# LEDS_BUTTONS.net
KiCad netlist of a schematic drawn in Altium Designer
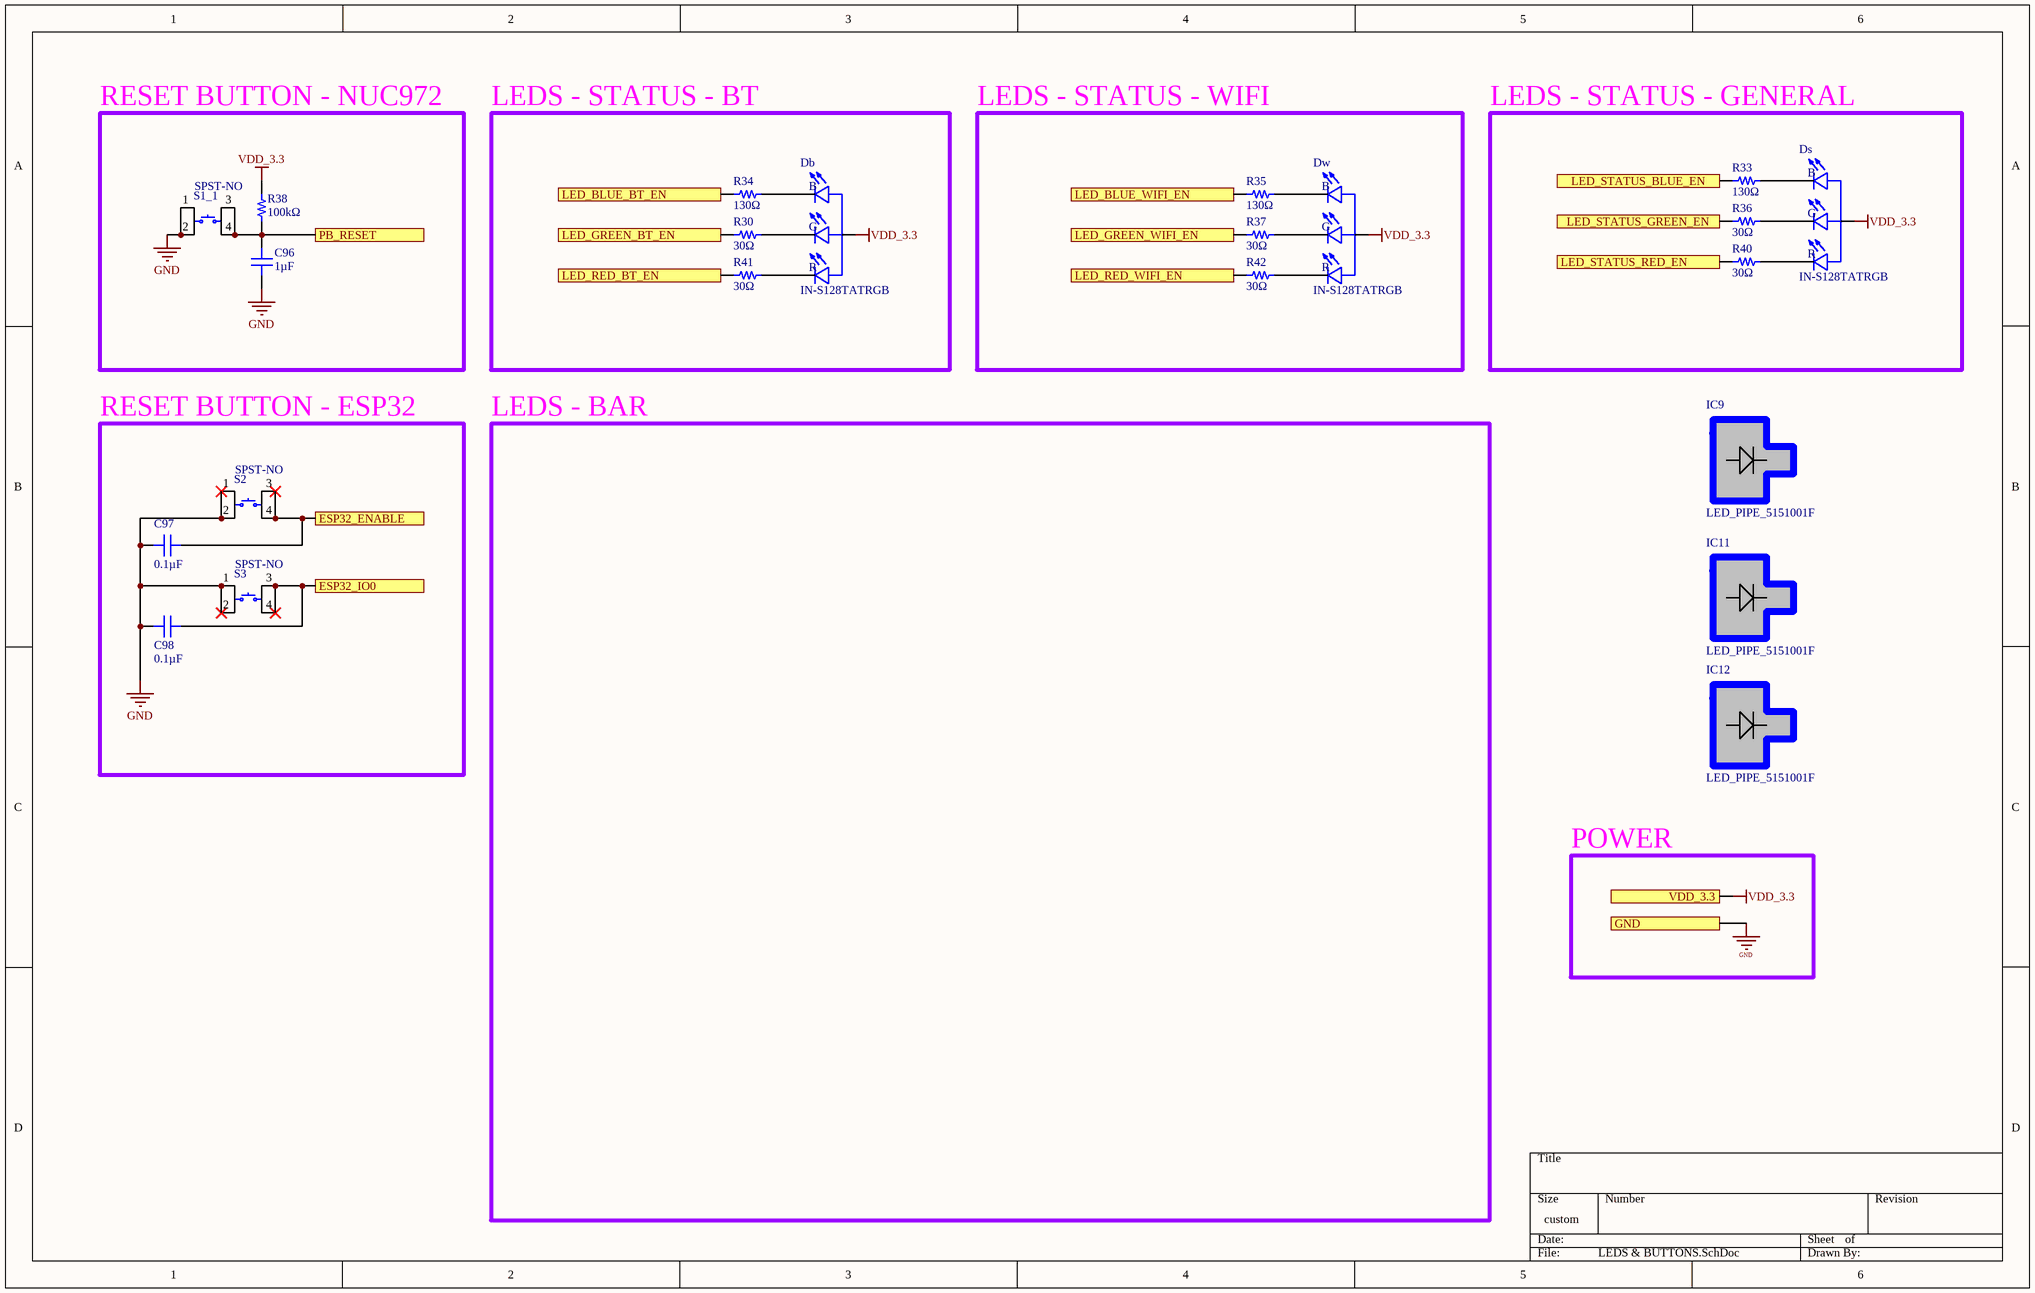
[diagram p0: LEDS & BUTTONS.SchDoc]

(export (version "E")
  (design (tool "Eeschema 10.0.6"))
  (components
    (comp (ref "C96")
      (value "1µF")
      (footprint "CAP 0603_1608")
      (description "CAP CER 1UF 10V X7R 0603")
      (fields (field (name "MANUFACTURER") "KEMET") (field (name "VOLTAGE") "10V"))
      (libsource (lib "MVVVMAltiumDatabase") (part "Capacitor"))
    )
    (comp (ref "C97")
      (value "0.1µF")
      (footprint "CAP 0603_1608 RF")
      (description "CAP CER 0.1UF 16V X7R 0603")
      (fields (field (name "MANUFACTURER") "KEMET") (field (name "VOLTAGE") "16V"))
      (libsource (lib "MVVVMAltiumDatabase") (part "Capacitor"))
    )
    (comp (ref "C98")
      (value "0.1µF")
      (footprint "CAP 0603_1608 RF")
      (description "CAP CER 0.1UF 16V X7R 0603")
      (fields (field (name "MANUFACTURER") "KEMET") (field (name "VOLTAGE") "16V"))
      (libsource (lib "MVVVMAltiumDatabase") (part "Capacitor"))
    )
    (comp (ref "Db")
      (value "IN-S128TATRGB")
      (footprint "LEDSC270X320X110-4N")
      (fields (field (name "MF") "Inolux"))
      (libsource (lib "IN-S128TATRGB") (part "IN-S128TATRGB"))
    )
    (comp (ref "Ds")
      (value "IN-S128TATRGB")
      (footprint "LEDSC270X320X110-4N")
      (fields (field (name "MF") "Inolux"))
      (libsource (lib "IN-S128TATRGB") (part "IN-S128TATRGB"))
    )
    (comp (ref "Dw")
      (value "IN-S128TATRGB")
      (footprint "LEDSC270X320X110-4N")
      (fields (field (name "MF") "Inolux"))
      (libsource (lib "IN-S128TATRGB") (part "IN-S128TATRGB"))
    )
    (comp (ref "IC9")
      (value "LED_PIPE_5151001F")
      (footprint "LED PIPE 5151001F")
      (libsource (lib "MVVVMAltiumDatabase") (part "LED_PIPE_5151001F"))
    )
    (comp (ref "IC11")
      (value "LED_PIPE_5151001F")
      (footprint "LED PIPE 5151001F")
      (libsource (lib "MVVVMAltiumDatabase") (part "LED_PIPE_5151001F"))
    )
    (comp (ref "IC12")
      (value "LED_PIPE_5151001F")
      (footprint "LED PIPE 5151001F")
      (libsource (lib "MVVVMAltiumDatabase") (part "LED_PIPE_5151001F"))
    )
    (comp (ref "R30")
      (value "30Ω")
      (footprint "RES 0603_1608 RF")
      (description "RES 30 OHM 1% 1/10W 0603")
      (fields (field (name "MANUFACTURER") "Vishay Dale") (field (name "TOLERANCE") "±1%"))
      (libsource (lib "MVVVMAltiumDatabase") (part "Resistor"))
    )
    (comp (ref "R33")
      (value "130Ω")
      (footprint "RES 0603_1608 RF")
      (description "RES 130 OHM 1% 1/10W 0603")
      (fields (field (name "MANUFACTURER") "Vishay Dale") (field (name "TOLERANCE") "±1%"))
      (libsource (lib "MVVVMAltiumDatabase") (part "Resistor"))
    )
    (comp (ref "R34")
      (value "130Ω")
      (footprint "RES 0603_1608 RF")
      (description "RES 130 OHM 1% 1/10W 0603")
      (fields (field (name "MANUFACTURER") "Vishay Dale") (field (name "TOLERANCE") "±1%"))
      (libsource (lib "MVVVMAltiumDatabase") (part "Resistor"))
    )
    (comp (ref "R35")
      (value "130Ω")
      (footprint "RES 0603_1608 RF")
      (description "RES 130 OHM 1% 1/10W 0603")
      (fields (field (name "MANUFACTURER") "Vishay Dale") (field (name "TOLERANCE") "±1%"))
      (libsource (lib "MVVVMAltiumDatabase") (part "Resistor"))
    )
    (comp (ref "R36")
      (value "30Ω")
      (footprint "RES 0603_1608 RF")
      (description "RES 30 OHM 1% 1/10W 0603")
      (fields (field (name "MANUFACTURER") "Vishay Dale") (field (name "TOLERANCE") "±1%"))
      (libsource (lib "MVVVMAltiumDatabase") (part "Resistor"))
    )
    (comp (ref "R37")
      (value "30Ω")
      (footprint "RES 0603_1608 RF")
      (description "RES 30 OHM 1% 1/10W 0603")
      (fields (field (name "MANUFACTURER") "Vishay Dale") (field (name "TOLERANCE") "±1%"))
      (libsource (lib "MVVVMAltiumDatabase") (part "Resistor"))
    )
    (comp (ref "R38")
      (value "100kΩ")
      (footprint "RES 0402_1005 RF")
      (description "RES SMD 100K OHM 1% 1/16W 0402")
      (fields (field (name "MANUFACTURER") "Vishay Dale") (field (name "TOLERANCE") "±1%"))
      (libsource (lib "MVVVMAltiumDatabase") (part "Resistor"))
    )
    (comp (ref "R40")
      (value "30Ω")
      (footprint "RES 0603_1608 RF")
      (description "RES 30 OHM 1% 1/10W 0603")
      (fields (field (name "MANUFACTURER") "Vishay Dale") (field (name "TOLERANCE") "±1%"))
      (libsource (lib "MVVVMAltiumDatabase") (part "Resistor"))
    )
    (comp (ref "R41")
      (value "30Ω")
      (footprint "RES 0603_1608 RF")
      (description "RES 30 OHM 1% 1/10W 0603")
      (fields (field (name "MANUFACTURER") "Vishay Dale") (field (name "TOLERANCE") "±1%"))
      (libsource (lib "MVVVMAltiumDatabase") (part "Resistor"))
    )
    (comp (ref "R42")
      (value "30Ω")
      (footprint "RES 0603_1608 RF")
      (description "RES 30 OHM 1% 1/10W 0603")
      (fields (field (name "MANUFACTURER") "Vishay Dale") (field (name "TOLERANCE") "±1%"))
      (libsource (lib "MVVVMAltiumDatabase") (part "Resistor"))
    )
    (comp (ref "S1_1")
      (value "SPST-NO")
      (footprint "TE FSM4JSMA")
      (description "SWITCH TACTILE SPST-NO 0.05A 24V")
      (fields (field (name "MANUFACTURER") "TE Connectivity ALCOSWITCH Switches"))
      (libsource (lib "MVVVMAltiumDatabase") (part "TE FSM4JSMA"))
    )
    (comp (ref "S2")
      (value "SPST-NO")
      (footprint "TE FSM4JSMA")
      (description "SWITCH TACTILE SPST-NO 0.05A 24V")
      (fields (field (name "MANUFACTURER") "TE Connectivity ALCOSWITCH Switches"))
      (libsource (lib "MVVVMAltiumDatabase") (part "TE FSM4JSMA"))
    )
    (comp (ref "S3")
      (value "SPST-NO")
      (footprint "TE FSM4JSMA")
      (description "SWITCH TACTILE SPST-NO 0.05A 24V")
      (fields (field (name "MANUFACTURER") "TE Connectivity ALCOSWITCH Switches"))
      (libsource (lib "MVVVMAltiumDatabase") (part "TE FSM4JSMA"))
    )
  )
  (nets
    (net (code "1") (name "/ESP32_ENABLE") (class "Default")
      (node (ref "C97") (pin "1") (pinfunction "1_1") (pintype "passive"))
      (node (ref "S2") (pin "3") (pinfunction "3_3") (pintype "passive"))
      (node (ref "S2") (pin "4") (pinfunction "4_4") (pintype "passive"))
    )
    (net (code "2") (name "/ESP32_IO0") (class "Default")
      (node (ref "C98") (pin "1") (pinfunction "1_1") (pintype "passive"))
      (node (ref "S3") (pin "3") (pinfunction "3_3") (pintype "passive"))
      (node (ref "S3") (pin "4") (pinfunction "4_4") (pintype "passive"))
    )
    (net (code "3") (name "/LED_BLUE_BT_EN") (class "Default")
      (node (ref "R34") (pin "1") (pinfunction "1_1") (pintype "passive"))
    )
    (net (code "4") (name "/LED_BLUE_WIFI_EN") (class "Default")
      (node (ref "R35") (pin "1") (pinfunction "1_1") (pintype "passive"))
    )
    (net (code "5") (name "/LED_GREEN_BT_EN") (class "Default")
      (node (ref "R30") (pin "1") (pinfunction "1_1") (pintype "passive"))
    )
    (net (code "6") (name "/LED_GREEN_WIFI_EN") (class "Default")
      (node (ref "R37") (pin "1") (pinfunction "1_1") (pintype "passive"))
    )
    (net (code "7") (name "/LED_RED_BT_EN") (class "Default")
      (node (ref "R41") (pin "1") (pinfunction "1_1") (pintype "passive"))
    )
    (net (code "8") (name "/LED_RED_WIFI_EN") (class "Default")
      (node (ref "R42") (pin "1") (pinfunction "1_1") (pintype "passive"))
    )
    (net (code "9") (name "/LED_STATUS_BLUE_EN") (class "Default")
      (node (ref "R33") (pin "1") (pinfunction "1_1") (pintype "passive"))
    )
    (net (code "10") (name "/LED_STATUS_GREEN_EN") (class "Default")
      (node (ref "R36") (pin "1") (pinfunction "1_1") (pintype "passive"))
    )
    (net (code "11") (name "/LED_STATUS_RED_EN") (class "Default")
      (node (ref "R40") (pin "1") (pinfunction "1_1") (pintype "passive"))
    )
    (net (code "12") (name "/PB_RESET") (class "Default")
      (node (ref "C96") (pin "2") (pinfunction "2_2") (pintype "passive"))
      (node (ref "R38") (pin "1") (pinfunction "1_1") (pintype "passive"))
      (node (ref "S1_1") (pin "3") (pinfunction "3_3") (pintype "passive"))
      (node (ref "S1_1") (pin "4") (pinfunction "4_4") (pintype "passive"))
    )
    (net (code "13") (name "GND") (class "Default")
      (node (ref "C96") (pin "1") (pinfunction "1_1") (pintype "passive"))
      (node (ref "C97") (pin "2") (pinfunction "2_2") (pintype "passive"))
      (node (ref "C98") (pin "2") (pinfunction "2_2") (pintype "passive"))
      (node (ref "S1_1") (pin "1") (pinfunction "1_1") (pintype "passive"))
      (node (ref "S1_1") (pin "2") (pinfunction "2_2") (pintype "passive"))
      (node (ref "S2") (pin "1") (pinfunction "1_1") (pintype "passive"))
      (node (ref "S2") (pin "2") (pinfunction "2_2") (pintype "passive"))
      (node (ref "S3") (pin "1") (pinfunction "1_1") (pintype "passive"))
      (node (ref "S3") (pin "2") (pinfunction "2_2") (pintype "passive"))
    )
    (net (code "14") (name "Net-(Db-Pad2)") (class "Default")
      (node (ref "Db") (pin "2") (pinfunction "2_2") (pintype "passive"))
      (node (ref "R34") (pin "2") (pinfunction "2_2") (pintype "passive"))
    )
    (net (code "15") (name "Net-(Db-Pad3)") (class "Default")
      (node (ref "Db") (pin "3") (pinfunction "3_3") (pintype "passive"))
      (node (ref "R41") (pin "2") (pinfunction "2_2") (pintype "passive"))
    )
    (net (code "16") (name "Net-(Db-Pad4)") (class "Default")
      (node (ref "Db") (pin "4") (pinfunction "4_4") (pintype "passive"))
      (node (ref "R30") (pin "2") (pinfunction "2_2") (pintype "passive"))
    )
    (net (code "17") (name "Net-(Ds-Pad2)") (class "Default")
      (node (ref "Ds") (pin "2") (pinfunction "2_2") (pintype "passive"))
      (node (ref "R33") (pin "2") (pinfunction "2_2") (pintype "passive"))
    )
    (net (code "18") (name "Net-(Ds-Pad3)") (class "Default")
      (node (ref "Ds") (pin "3") (pinfunction "3_3") (pintype "passive"))
      (node (ref "R40") (pin "2") (pinfunction "2_2") (pintype "passive"))
    )
    (net (code "19") (name "Net-(Ds-Pad4)") (class "Default")
      (node (ref "Ds") (pin "4") (pinfunction "4_4") (pintype "passive"))
      (node (ref "R36") (pin "2") (pinfunction "2_2") (pintype "passive"))
    )
    (net (code "20") (name "Net-(Dw-Pad2)") (class "Default")
      (node (ref "Dw") (pin "2") (pinfunction "2_2") (pintype "passive"))
      (node (ref "R35") (pin "2") (pinfunction "2_2") (pintype "passive"))
    )
    (net (code "21") (name "Net-(Dw-Pad3)") (class "Default")
      (node (ref "Dw") (pin "3") (pinfunction "3_3") (pintype "passive"))
      (node (ref "R42") (pin "2") (pinfunction "2_2") (pintype "passive"))
    )
    (net (code "22") (name "Net-(Dw-Pad4)") (class "Default")
      (node (ref "Dw") (pin "4") (pinfunction "4_4") (pintype "passive"))
      (node (ref "R37") (pin "2") (pinfunction "2_2") (pintype "passive"))
    )
    (net (code "23") (name "VDD_3.3") (class "Default")
      (node (ref "Db") (pin "1") (pinfunction "1_1") (pintype "passive"))
      (node (ref "Ds") (pin "1") (pinfunction "1_1") (pintype "passive"))
      (node (ref "Dw") (pin "1") (pinfunction "1_1") (pintype "passive"))
      (node (ref "R38") (pin "2") (pinfunction "2_2") (pintype "passive"))
    )
  )
)
